# isoSPI_Interface.net
KiCad netlist of a schematic drawn in Altium Designer
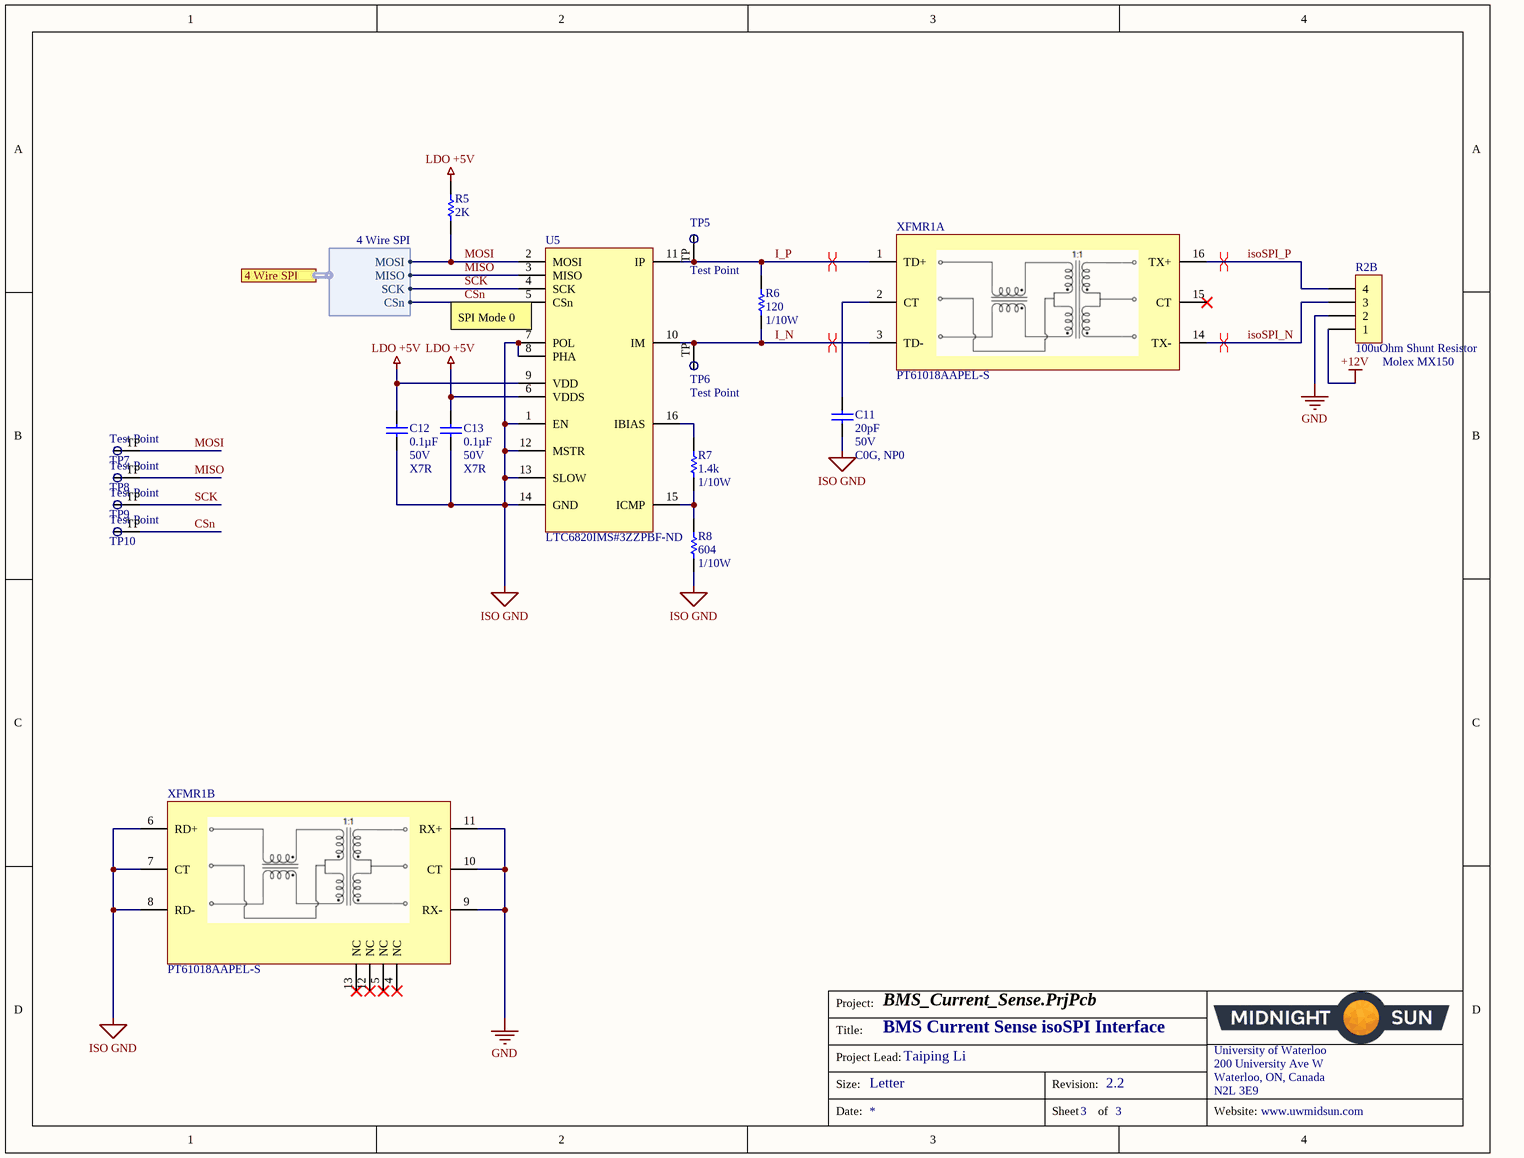
[diagram p0: isoSPI_Interface.SchDoc]

(export (version "E")
  (design (tool "Eeschema 10.0.6"))
  (components
    (comp (ref "C11")
      (value "CAP CER 20PF 50V ±5% C0G/NP0 0603")
      (footprint "CAP, 0603")
      (description "20pF ±5% 50V Ceramic Capacitor C0G, NP0 0603 (1608 Metric)")
      (fields
        (field (name "TOLERANCE") "±5%")
        (field (name "CAPACITANCE") "20pF")
        (field (name "VOLTAGE") "50V")
        (field (name "TEMPERATURE COEFFICIENT") "C0G, NP0")
      )
      (libsource (lib "Schematic Diagrams") (part "CAP CER 20PF 50V ±5% C0G/NP0 0603"))
    )
    (comp (ref "C12")
      (value "CAP CER 0.1UF 50V 10% X7R 0603")
      (footprint "CAP, 0603")
      (description "0.10µF ±10% 50V Ceramic Capacitor X7R 0603 (1608 Metric)")
      (fields
        (field (name "TOLERANCE") "±10%")
        (field (name "CAPACITANCE") "0.1µF")
        (field (name "VOLTAGE") "50V")
        (field (name "TEMPERATURE COEFFICIENT") "X7R")
      )
      (libsource (lib "Schematic Diagrams") (part "CAP CER 0.1UF 50V 10% X7R 0603"))
    )
    (comp (ref "C13")
      (value "CAP CER 0.1UF 50V 10% X7R 0603")
      (footprint "CAP, 0603")
      (description "0.10µF ±10% 50V Ceramic Capacitor X7R 0603 (1608 Metric)")
      (fields
        (field (name "TOLERANCE") "±10%")
        (field (name "CAPACITANCE") "0.1µF")
        (field (name "VOLTAGE") "50V")
        (field (name "TEMPERATURE COEFFICIENT") "X7R")
      )
      (libsource (lib "Schematic Diagrams") (part "CAP CER 0.1UF 50V 10% X7R 0603"))
    )
    (comp (ref "R2")
      (value "100uOhm Shunt Resistor")
      (footprint "RES SHUNT 100UOHM 60MM")
      (fields (field (name "TOLERANCE") "±5%"))
      (libsource (lib "Schematic Diagrams") (part "RES SHUNT 100UOHM 5% 36W 60MM"))
    )
    (comp (ref "R5")
      (value "2K")
      (footprint "RES, 0603")
      (description "2k Ohm ±1% 0.1W, 1/10W Chip Resistor 0603 (1608 Metric) Moisture Resistant Thick Film")
      (fields
        (field (name "MANUFACTURER") "Yageo")
        (field (name "MANUFACTURER PART NUMBER") "RC0603FR-072KL")
      )
      (libsource (lib "Schematic Diagrams") (part "RES 2K OHM 1% 1/10W 0603"))
    )
    (comp (ref "R6")
      (value "RES 120 OHM 1% 1/10W 0603")
      (footprint "RES, 0603")
      (description "RES SMD 120 OHM 1% 1/10W 0603")
      (fields
        (field (name "TOLERANCE") "±1%")
        (field (name "RESISTANCE") "120")
        (field (name "POWER") "1/10W")
      )
      (libsource (lib "Schematic Diagrams") (part "RES 120 OHM 1% 1/10W 0603"))
    )
    (comp (ref "R7")
      (value "RES 1.4k OHM 1% 1/10W 0603")
      (footprint "RES, 0603")
      (description "RES SMD 1.4K OHM 1% 1/10W 0603")
      (fields
        (field (name "TOLERANCE") "±1%")
        (field (name "RESISTANCE") "1.4k")
        (field (name "POWER") "1/10W")
      )
      (libsource (lib "Schematic Diagrams") (part "RES 1.4k OHM 1% 1/10W 0603"))
    )
    (comp (ref "R8")
      (value "RES 604 OHM 1% 1/10W 0603")
      (footprint "RES, 0603")
      (description "RES SMD 604 OHM 1% 1/10W 0603")
      (fields
        (field (name "TOLERANCE") "±1%")
        (field (name "RESISTANCE") "604")
        (field (name "POWER") "1/10W")
      )
      (libsource (lib "Schematic Diagrams") (part "RES 604 OHM 1% 1/10W 0603"))
    )
    (comp (ref "TP5")
      (value "Test Point")
      (footprint "Test Point")
      (libsource (lib "Schematic Diagrams") (part "Test Point"))
    )
    (comp (ref "TP6")
      (value "Test Point")
      (footprint "Test Point")
      (libsource (lib "Schematic Diagrams") (part "Test Point"))
    )
    (comp (ref "TP7")
      (value "Test Point")
      (footprint "Test Point")
      (libsource (lib "Schematic Diagrams") (part "Test Point"))
    )
    (comp (ref "TP8")
      (value "Test Point")
      (footprint "Test Point")
      (libsource (lib "Schematic Diagrams") (part "Test Point"))
    )
    (comp (ref "TP9")
      (value "Test Point")
      (footprint "Test Point")
      (libsource (lib "Schematic Diagrams") (part "Test Point"))
    )
    (comp (ref "TP10")
      (value "Test Point")
      (footprint "Test Point")
      (libsource (lib "Schematic Diagrams") (part "Test Point"))
    )
    (comp (ref "U5")
      (value "IC ISOSPI COMM INTERFACE LTC6820IMS#3ZZPBF")
      (footprint "IC isoSPI Interface LTC6820 MSOP")
      (description "IC COMM INTERFACE ISOSPI 16-MSOP")
      (fields
        (field (name "MANUFACTURER") "Linear Technology")
        (field (name "MANUFACTURER PART NUMBER") "LTC6820IMS#3ZZPBF")
        (field (name "SUPPLIER PART NUMBER 1") "LTC6820IMS#3ZZPBF-ND")
      )
      (libsource (lib "Schematic Diagrams") (part "IC ISOSPI COMM INTERFACE LTC6820IMS#3ZZPBF"))
    )
    (comp (ref "XFMR1")
      (value "IC PULSE XFMR 1CT:1CT 350UH SMD")
      (footprint "IC, PULSE XFMR 1CT:1CT 350UH SMD")
      (description "PULSE XFMR 1CT:1CT 350UH SMD")
      (fields (field (name "MANUFACTURER") "Bourns Inc.") (field (name "MFG_PN") "PT61018AAPEL-S"))
      (libsource (lib "Schematic Diagrams") (part "IC PULSE XFMR 1CT{colon}1CT 350UH SMD"))
    )
  )
  (nets
    (net (code "4") (name "+12V") (class "Default")
      (node (ref "R2") (pin "1") (pinfunction "1_1") (pintype "passive"))
    )
    (net (code "5") (name "/CSn") (class "Default")
      (node (ref "TP10") (pin "TP") (pinfunction "1_TP") (pintype "passive"))
      (node (ref "U5") (pin "5") (pinfunction "CSn_5") (pintype "passive"))
    )
    (net (code "6") (name "/I_N") (class "Default")
      (node (ref "R6") (pin "2") (pinfunction "2_2") (pintype "passive"))
      (node (ref "TP6") (pin "TP") (pinfunction "1_TP") (pintype "passive"))
      (node (ref "U5") (pin "10") (pinfunction "IM_10") (pintype "passive"))
      (node (ref "XFMR1") (pin "3") (pinfunction "TD-_3") (pintype "passive"))
    )
    (net (code "7") (name "/I_P") (class "Default")
      (node (ref "R6") (pin "1") (pinfunction "1_1") (pintype "passive"))
      (node (ref "TP5") (pin "TP") (pinfunction "1_TP") (pintype "passive"))
      (node (ref "U5") (pin "11") (pinfunction "IP_11") (pintype "passive"))
      (node (ref "XFMR1") (pin "1") (pinfunction "TD+_1") (pintype "passive"))
    )
    (net (code "8") (name "/MISO") (class "Default")
      (node (ref "TP8") (pin "TP") (pinfunction "1_TP") (pintype "passive"))
      (node (ref "U5") (pin "3") (pinfunction "MISO_3") (pintype "passive"))
    )
    (net (code "9") (name "/MOSI") (class "Default")
      (node (ref "R5") (pin "2") (pinfunction "2_2") (pintype "passive"))
      (node (ref "TP7") (pin "TP") (pinfunction "1_TP") (pintype "passive"))
      (node (ref "U5") (pin "2") (pinfunction "MOSI_2") (pintype "passive"))
    )
    (net (code "10") (name "/SCK") (class "Default")
      (node (ref "TP9") (pin "TP") (pinfunction "1_TP") (pintype "passive"))
      (node (ref "U5") (pin "4") (pinfunction "SCK_4") (pintype "passive"))
    )
    (net (code "11") (name "/isoSPI_N") (class "Default")
      (node (ref "R2") (pin "3") (pinfunction "3_3") (pintype "passive"))
      (node (ref "XFMR1") (pin "14") (pinfunction "TX-_14") (pintype "passive"))
    )
    (net (code "12") (name "/isoSPI_P") (class "Default")
      (node (ref "R2") (pin "4") (pinfunction "4_4") (pintype "passive"))
      (node (ref "XFMR1") (pin "16") (pinfunction "TX+_16") (pintype "passive"))
    )
    (net (code "14") (name "GND") (class "Default")
      (node (ref "R2") (pin "2") (pinfunction "2_2") (pintype "passive"))
      (node (ref "XFMR1") (pin "10") (pinfunction "CT_10") (pintype "passive"))
      (node (ref "XFMR1") (pin "11") (pinfunction "RX+_11") (pintype "passive"))
      (node (ref "XFMR1") (pin "9") (pinfunction "RX-_9") (pintype "passive"))
    )
    (net (code "15") (name "ISO GND") (class "Default")
      (node (ref "C11") (pin "2") (pinfunction "2_2") (pintype "passive"))
      (node (ref "C12") (pin "2") (pinfunction "2_2") (pintype "passive"))
      (node (ref "C13") (pin "2") (pinfunction "2_2") (pintype "passive"))
      (node (ref "R8") (pin "2") (pinfunction "2_2") (pintype "passive"))
      (node (ref "U5") (pin "1") (pinfunction "EN_1") (pintype "passive"))
      (node (ref "U5") (pin "12") (pinfunction "MSTR_12") (pintype "passive"))
      (node (ref "U5") (pin "13") (pinfunction "SLOW_13") (pintype "passive"))
      (node (ref "U5") (pin "14") (pinfunction "GND_14") (pintype "passive"))
      (node (ref "U5") (pin "7") (pinfunction "POL_7") (pintype "passive"))
      (node (ref "U5") (pin "8") (pinfunction "PHA_8") (pintype "passive"))
      (node (ref "XFMR1") (pin "6") (pinfunction "RD+_6") (pintype "passive"))
      (node (ref "XFMR1") (pin "7") (pinfunction "CT_7") (pintype "passive"))
      (node (ref "XFMR1") (pin "8") (pinfunction "RD-_8") (pintype "passive"))
    )
    (net (code "16") (name "LDO +5V") (class "Default")
      (node (ref "C12") (pin "1") (pinfunction "1_1") (pintype "passive"))
      (node (ref "C13") (pin "1") (pinfunction "1_1") (pintype "passive"))
      (node (ref "R5") (pin "1") (pinfunction "1_1") (pintype "passive"))
      (node (ref "U5") (pin "6") (pinfunction "VDDS_6") (pintype "passive"))
      (node (ref "U5") (pin "9") (pinfunction "VDD_9") (pintype "passive"))
    )
    (net (code "17") (name "Net-(C11-Pad1)") (class "Default")
      (node (ref "C11") (pin "1") (pinfunction "1_1") (pintype "passive"))
      (node (ref "XFMR1") (pin "2") (pinfunction "CT_2") (pintype "passive"))
    )
    (net (code "18") (name "Net-(U5-IBIAS)") (class "Default")
      (node (ref "R7") (pin "1") (pinfunction "1_1") (pintype "passive"))
      (node (ref "U5") (pin "16") (pinfunction "IBIAS_16") (pintype "passive"))
    )
    (net (code "19") (name "Net-(U5-ICMP)") (class "Default")
      (node (ref "R7") (pin "2") (pinfunction "2_2") (pintype "passive"))
      (node (ref "R8") (pin "1") (pinfunction "1_1") (pintype "passive"))
      (node (ref "U5") (pin "15") (pinfunction "ICMP_15") (pintype "passive"))
    )
    (net (code "20") (name "unconnected-(XFMR1A-CT-Pad15)") (class "Default")
      (node (ref "XFMR1") (pin "15") (pinfunction "CT_15") (pintype "passive+no_connect"))
    )
    (net (code "21") (name "unconnected-(XFMR1B-NC-Pad4)") (class "Default")
      (node (ref "XFMR1") (pin "4") (pinfunction "NC_4") (pintype "passive+no_connect"))
    )
    (net (code "22") (name "unconnected-(XFMR1B-NC-Pad5)") (class "Default")
      (node (ref "XFMR1") (pin "5") (pinfunction "NC_5") (pintype "passive+no_connect"))
    )
    (net (code "23") (name "unconnected-(XFMR1B-NC-Pad12)") (class "Default")
      (node (ref "XFMR1") (pin "12") (pinfunction "NC_12") (pintype "passive+no_connect"))
    )
    (net (code "24") (name "unconnected-(XFMR1B-NC-Pad13)") (class "Default")
      (node (ref "XFMR1") (pin "13") (pinfunction "NC_13") (pintype "passive+no_connect"))
    )
  )
)
